# l.net
KiCad netlist of a schematic drawn in EAGLE
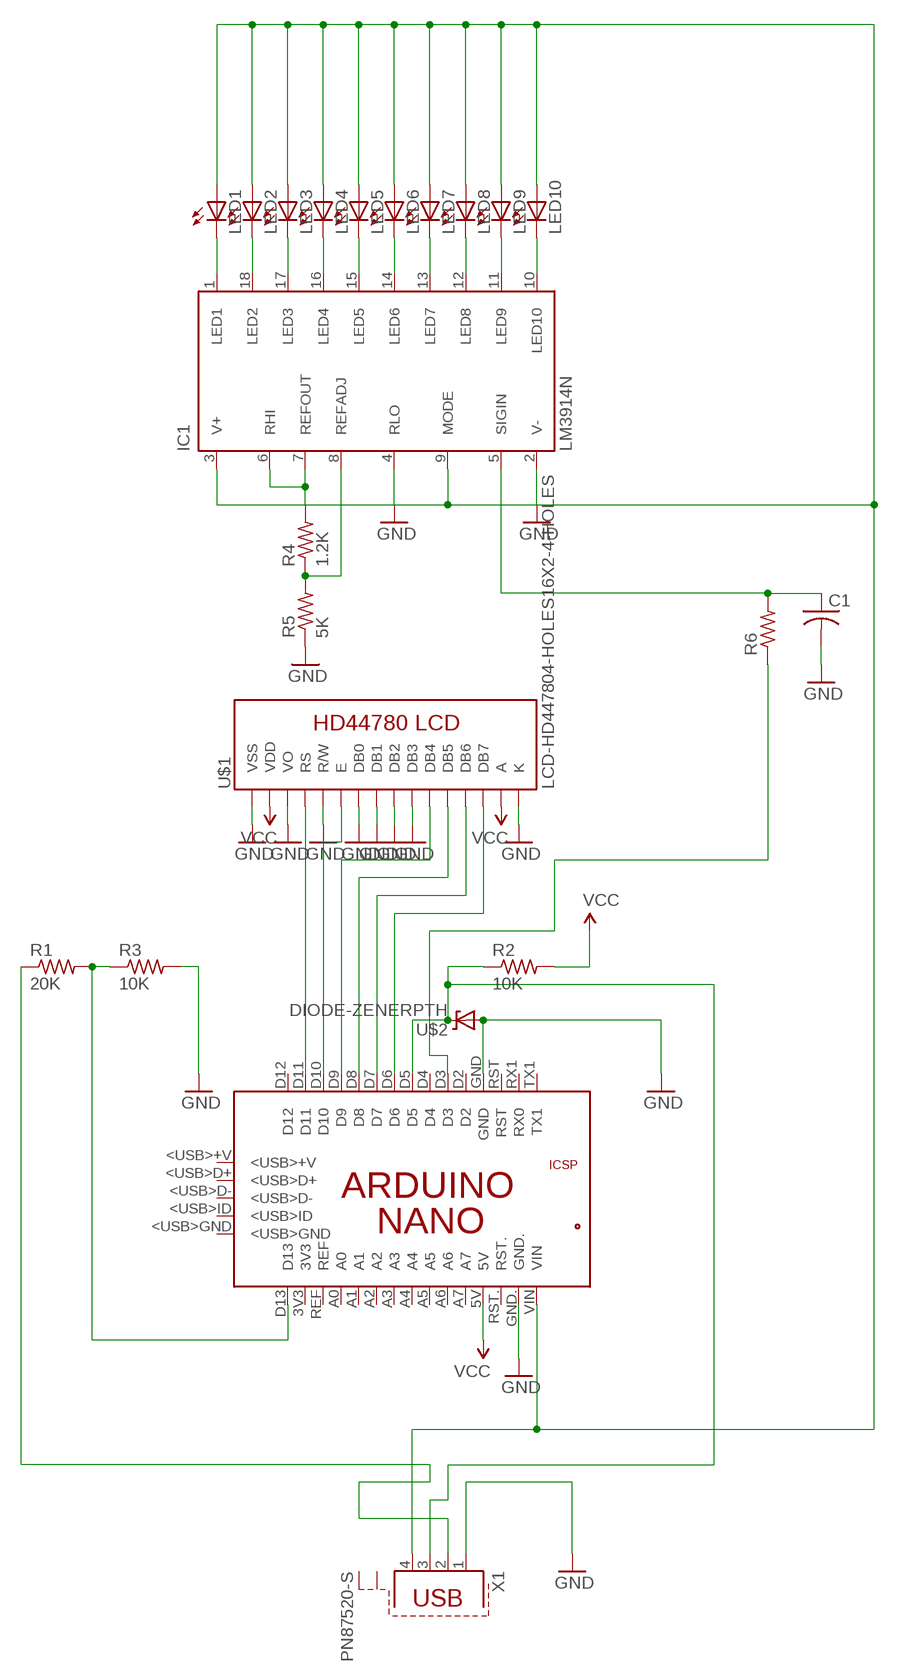
[diagram p0: schematic, sheet 1]

(export (version "E")
  (design (tool "Eeschema 10.0.6"))
  (components
    (comp (ref "C1")
      (value "C-US025-040X050")
      (footprint "eagle-import:C025-040X050")
      (libsource (lib "eagle-import") (part "C-US025-040X050"))
    )
    (comp (ref "IC1")
      (value "LM3914N")
      (footprint "eagle-import:DIL18")
      (libsource (lib "eagle-import") (part "LM391N4"))
    )
    (comp (ref "LED1")
      (value "LED5MM")
      (footprint "eagle-import:LED5MM")
      (libsource (lib "eagle-import") (part "LED5MM"))
    )
    (comp (ref "LED2")
      (value "LED5MM")
      (footprint "eagle-import:LED5MM")
      (libsource (lib "eagle-import") (part "LED5MM"))
    )
    (comp (ref "LED3")
      (value "LED5MM")
      (footprint "eagle-import:LED5MM")
      (libsource (lib "eagle-import") (part "LED5MM"))
    )
    (comp (ref "LED4")
      (value "LED5MM")
      (footprint "eagle-import:LED5MM")
      (libsource (lib "eagle-import") (part "LED5MM"))
    )
    (comp (ref "LED5")
      (value "LED5MM")
      (footprint "eagle-import:LED5MM")
      (libsource (lib "eagle-import") (part "LED5MM"))
    )
    (comp (ref "LED6")
      (value "LED5MM")
      (footprint "eagle-import:LED5MM")
      (libsource (lib "eagle-import") (part "LED5MM"))
    )
    (comp (ref "LED7")
      (value "LED5MM")
      (footprint "eagle-import:LED5MM")
      (libsource (lib "eagle-import") (part "LED5MM"))
    )
    (comp (ref "LED8")
      (value "LED5MM")
      (footprint "eagle-import:LED5MM")
      (libsource (lib "eagle-import") (part "LED5MM"))
    )
    (comp (ref "LED9")
      (value "LED5MM")
      (footprint "eagle-import:LED5MM")
      (libsource (lib "eagle-import") (part "LED5MM"))
    )
    (comp (ref "LED10")
      (value "LED5MM")
      (footprint "eagle-import:LED5MM")
      (libsource (lib "eagle-import") (part "LED5MM"))
    )
    (comp (ref "PCB1")
      (value "ARDUINO_NANO")
      (footprint "eagle-import:ARDUINO_NANO")
      (libsource (lib "eagle-import") (part "ARDUINO_NANO"))
    )
    (comp (ref "R1")
      (value "20K")
      (footprint "eagle-import:0204_7")
      (libsource (lib "eagle-import") (part "R-US_0204/7"))
    )
    (comp (ref "R2")
      (value "10K")
      (footprint "eagle-import:0204_7")
      (libsource (lib "eagle-import") (part "R-US_0204/7"))
    )
    (comp (ref "R3")
      (value "10K")
      (footprint "eagle-import:0204_7")
      (libsource (lib "eagle-import") (part "R-US_0204/7"))
    )
    (comp (ref "R4")
      (value "1.2K")
      (footprint "eagle-import:0204_7")
      (libsource (lib "eagle-import") (part "R-US_0204/7"))
    )
    (comp (ref "R5")
      (value "5K")
      (footprint "eagle-import:0204_7")
      (libsource (lib "eagle-import") (part "R-US_0204/7"))
    )
    (comp (ref "R6")
      (value "R-US_0204/7")
      (footprint "eagle-import:0204_7")
      (libsource (lib "eagle-import") (part "R-US_0204/7"))
    )
    (comp (ref "U$1")
      (value "LCD-HD447804-HOLES16X2-4-HOLES")
      (footprint "eagle-import:LCD-16X2-4HOLES")
      (libsource (lib "eagle-import") (part "LCD-HD4478016X2-4-HOLES4-HOLES"))
    )
    (comp (ref "U$2")
      (value "DIODE-ZENERPTH")
      (footprint "eagle-import:DIODE-ZENER")
      (libsource (lib "eagle-import") (part "DIODE-ZENERPTH"))
    )
    (comp (ref "X1")
      (value "PN87520-S")
      (footprint "eagle-import:PN87520-S")
      (libsource (lib "eagle-import") (part "PN87520-S"))
    )
  )
  (nets
    (net (code "1") (name "GND") (class "Default")
      (node (ref "C1") (pin "2") (pinfunction "2_2") (pintype "passive"))
      (node (ref "IC1") (pin "2") (pinfunction "V-_2") (pintype "power_in"))
      (node (ref "IC1") (pin "4") (pinfunction "RLO_4") (pintype "input"))
      (node (ref "PCB1") (pin "GND") (pinfunction "GND_GND") (pintype "bidirectional"))
      (node (ref "PCB1") (pin "GND.") (pinfunction "GND._GND.") (pintype "bidirectional"))
      (node (ref "R3") (pin "2") (pinfunction "2_2") (pintype "passive"))
      (node (ref "R5") (pin "1") (pinfunction "1_1") (pintype "passive"))
      (node (ref "U$1") (pin "1") (pinfunction "VSS_1") (pintype "power_in"))
      (node (ref "U$1") (pin "10") (pinfunction "DB3_10") (pintype "bidirectional"))
      (node (ref "U$1") (pin "16") (pinfunction "K_16") (pintype "power_in"))
      (node (ref "U$1") (pin "3") (pinfunction "VO_3") (pintype "bidirectional"))
      (node (ref "U$1") (pin "5") (pinfunction "R/W_5") (pintype "input"))
      (node (ref "U$1") (pin "7") (pinfunction "DB0_7") (pintype "bidirectional"))
      (node (ref "U$1") (pin "8") (pinfunction "DB1_8") (pintype "bidirectional"))
      (node (ref "U$1") (pin "9") (pinfunction "DB2_9") (pintype "bidirectional"))
      (node (ref "U$2") (pin "P$2") (pinfunction "A_P$2") (pintype "passive"))
      (node (ref "X1") (pin "1") (pinfunction "1_1") (pintype "passive"))
    )
    (net (code "2") (name "Net-(IC1-LED1)") (class "Default")
      (node (ref "IC1") (pin "1") (pinfunction "LED1_1") (pintype "output"))
      (node (ref "LED1") (pin "K") (pinfunction "C_K") (pintype "passive"))
    )
    (net (code "3") (name "Net-(IC1-LED2)") (class "Default")
      (node (ref "IC1") (pin "18") (pinfunction "LED2_18") (pintype "output"))
      (node (ref "LED2") (pin "K") (pinfunction "C_K") (pintype "passive"))
    )
    (net (code "4") (name "Net-(IC1-LED3)") (class "Default")
      (node (ref "IC1") (pin "17") (pinfunction "LED3_17") (pintype "output"))
      (node (ref "LED3") (pin "K") (pinfunction "C_K") (pintype "passive"))
    )
    (net (code "5") (name "Net-(IC1-LED4)") (class "Default")
      (node (ref "IC1") (pin "16") (pinfunction "LED4_16") (pintype "output"))
      (node (ref "LED4") (pin "K") (pinfunction "C_K") (pintype "passive"))
    )
    (net (code "6") (name "Net-(IC1-LED5)") (class "Default")
      (node (ref "IC1") (pin "15") (pinfunction "LED5_15") (pintype "output"))
      (node (ref "LED5") (pin "K") (pinfunction "C_K") (pintype "passive"))
    )
    (net (code "7") (name "Net-(IC1-LED6)") (class "Default")
      (node (ref "IC1") (pin "14") (pinfunction "LED6_14") (pintype "output"))
      (node (ref "LED6") (pin "K") (pinfunction "C_K") (pintype "passive"))
    )
    (net (code "8") (name "Net-(IC1-LED7)") (class "Default")
      (node (ref "IC1") (pin "13") (pinfunction "LED7_13") (pintype "output"))
      (node (ref "LED7") (pin "K") (pinfunction "C_K") (pintype "passive"))
    )
    (net (code "9") (name "Net-(IC1-LED8)") (class "Default")
      (node (ref "IC1") (pin "12") (pinfunction "LED8_12") (pintype "output"))
      (node (ref "LED8") (pin "K") (pinfunction "C_K") (pintype "passive"))
    )
    (net (code "10") (name "Net-(IC1-LED9)") (class "Default")
      (node (ref "IC1") (pin "11") (pinfunction "LED9_11") (pintype "output"))
      (node (ref "LED9") (pin "K") (pinfunction "C_K") (pintype "passive"))
    )
    (net (code "11") (name "Net-(IC1-LED10)") (class "Default")
      (node (ref "IC1") (pin "10") (pinfunction "LED10_10") (pintype "output"))
      (node (ref "LED10") (pin "K") (pinfunction "C_K") (pintype "passive"))
    )
    (net (code "12") (name "Net-(IC1-MODE)") (class "Default")
      (node (ref "IC1") (pin "3") (pinfunction "V+_3") (pintype "power_in"))
      (node (ref "IC1") (pin "9") (pinfunction "MODE_9") (pintype "input"))
      (node (ref "LED1") (pin "A") (pinfunction "A_A") (pintype "passive"))
      (node (ref "LED10") (pin "A") (pinfunction "A_A") (pintype "passive"))
      (node (ref "LED2") (pin "A") (pinfunction "A_A") (pintype "passive"))
      (node (ref "LED3") (pin "A") (pinfunction "A_A") (pintype "passive"))
      (node (ref "LED4") (pin "A") (pinfunction "A_A") (pintype "passive"))
      (node (ref "LED5") (pin "A") (pinfunction "A_A") (pintype "passive"))
      (node (ref "LED6") (pin "A") (pinfunction "A_A") (pintype "passive"))
      (node (ref "LED7") (pin "A") (pinfunction "A_A") (pintype "passive"))
      (node (ref "LED8") (pin "A") (pinfunction "A_A") (pintype "passive"))
      (node (ref "LED9") (pin "A") (pinfunction "A_A") (pintype "passive"))
      (node (ref "PCB1") (pin "VIN") (pinfunction "VIN_VIN") (pintype "bidirectional"))
      (node (ref "X1") (pin "4") (pinfunction "4_4") (pintype "passive"))
    )
    (net (code "13") (name "Net-(IC1-REFADJ)") (class "Default")
      (node (ref "IC1") (pin "8") (pinfunction "REFADJ_8") (pintype "passive"))
      (node (ref "R4") (pin "1") (pinfunction "1_1") (pintype "passive"))
      (node (ref "R5") (pin "2") (pinfunction "2_2") (pintype "passive"))
    )
    (net (code "14") (name "Net-(IC1-REFOUT)") (class "Default")
      (node (ref "IC1") (pin "6") (pinfunction "RHI_6") (pintype "input"))
      (node (ref "IC1") (pin "7") (pinfunction "REFOUT_7") (pintype "output"))
      (node (ref "R4") (pin "2") (pinfunction "2_2") (pintype "passive"))
    )
    (net (code "15") (name "Net-(IC1-SIGIN)") (class "Default")
      (node (ref "C1") (pin "1") (pinfunction "1_1") (pintype "passive"))
      (node (ref "IC1") (pin "5") (pinfunction "SIGIN_5") (pintype "input"))
      (node (ref "R6") (pin "2") (pinfunction "2_2") (pintype "passive"))
    )
    (net (code "16") (name "Net-(PCB1-PadD3)") (class "Default")
      (node (ref "PCB1") (pin "D3") (pinfunction "D3_D3") (pintype "bidirectional"))
      (node (ref "R6") (pin "1") (pinfunction "1_1") (pintype "passive"))
    )
    (net (code "17") (name "Net-(PCB1-PadD13)") (class "Default")
      (node (ref "PCB1") (pin "D13") (pinfunction "D13_D13") (pintype "bidirectional"))
      (node (ref "R1") (pin "2") (pinfunction "2_2") (pintype "passive"))
      (node (ref "R3") (pin "1") (pinfunction "1_1") (pintype "passive"))
    )
    (net (code "18") (name "Net-(R1-Pad1)") (class "Default")
      (node (ref "R1") (pin "1") (pinfunction "1_1") (pintype "passive"))
      (node (ref "X1") (pin "2") (pinfunction "2_2") (pintype "passive"))
    )
    (net (code "19") (name "Net-(U$1-DB4)") (class "Default")
      (node (ref "PCB1") (pin "D9") (pinfunction "D9_D9") (pintype "bidirectional"))
      (node (ref "U$1") (pin "11") (pinfunction "DB4_11") (pintype "bidirectional"))
    )
    (net (code "20") (name "Net-(U$1-DB5)") (class "Default")
      (node (ref "PCB1") (pin "D8") (pinfunction "D8_D8") (pintype "bidirectional"))
      (node (ref "U$1") (pin "12") (pinfunction "DB5_12") (pintype "bidirectional"))
    )
    (net (code "21") (name "Net-(U$1-DB6)") (class "Default")
      (node (ref "PCB1") (pin "D7") (pinfunction "D7_D7") (pintype "bidirectional"))
      (node (ref "U$1") (pin "13") (pinfunction "DB6_13") (pintype "bidirectional"))
    )
    (net (code "22") (name "Net-(U$1-DB7)") (class "Default")
      (node (ref "PCB1") (pin "D6") (pinfunction "D6_D6") (pintype "bidirectional"))
      (node (ref "U$1") (pin "14") (pinfunction "DB7_14") (pintype "bidirectional"))
    )
    (net (code "23") (name "Net-(U$1-E)") (class "Default")
      (node (ref "PCB1") (pin "D10") (pinfunction "D10_D10") (pintype "bidirectional"))
      (node (ref "U$1") (pin "6") (pinfunction "E_6") (pintype "input"))
    )
    (net (code "24") (name "Net-(U$1-RS)") (class "Default")
      (node (ref "PCB1") (pin "D11") (pinfunction "D11_D11") (pintype "bidirectional"))
      (node (ref "U$1") (pin "4") (pinfunction "RS_4") (pintype "input"))
    )
    (net (code "25") (name "Net-(U$2-C)") (class "Default")
      (node (ref "PCB1") (pin "D5") (pinfunction "D5_D5") (pintype "bidirectional"))
      (node (ref "R2") (pin "1") (pinfunction "1_1") (pintype "passive"))
      (node (ref "U$2") (pin "P$1") (pinfunction "C_P$1") (pintype "passive"))
      (node (ref "X1") (pin "3") (pinfunction "3_3") (pintype "passive"))
    )
    (net (code "26") (name "VCC") (class "Default")
      (node (ref "PCB1") (pin "5V") (pinfunction "5V_5V") (pintype "bidirectional"))
      (node (ref "R2") (pin "2") (pinfunction "2_2") (pintype "passive"))
      (node (ref "U$1") (pin "15") (pinfunction "A_15") (pintype "power_in"))
      (node (ref "U$1") (pin "2") (pinfunction "VDD_2") (pintype "power_in"))
    )
    (net (code "27") (name "unconnected-(PCB1-Pad3V3)") (class "Default")
      (node (ref "PCB1") (pin "3V3") (pinfunction "3V3_3V3") (pintype "bidirectional"))
    )
    (net (code "28") (name "unconnected-(PCB1-Pad5V.)") (class "Default")
      (node (ref "PCB1") (pin "5V.") (pinfunction "5V._5V.") (pintype "bidirectional"))
    )
    (net (code "29") (name "unconnected-(PCB1-Pad<USB>+V)") (class "Default")
      (node (ref "PCB1") (pin "<USB>+V") (pinfunction "<USB>+V_<USB>+V") (pintype "bidirectional"))
    )
    (net (code "30") (name "unconnected-(PCB1-Pad<USB>D+)") (class "Default")
      (node (ref "PCB1") (pin "<USB>D+") (pinfunction "<USB>D+_<USB>D+") (pintype "bidirectional"))
    )
    (net (code "31") (name "unconnected-(PCB1-Pad<USB>D-)") (class "Default")
      (node (ref "PCB1") (pin "<USB>D-") (pinfunction "<USB>D-_<USB>D-") (pintype "bidirectional"))
    )
    (net (code "32") (name "unconnected-(PCB1-Pad<USB>GND)") (class "Default")
      (node (ref "PCB1") (pin "<USB>GND") (pinfunction "<USB>GND_<USB>GND") (pintype "bidirectional"))
    )
    (net (code "33") (name "unconnected-(PCB1-Pad<USB>ID)") (class "Default")
      (node (ref "PCB1") (pin "<USB>ID") (pinfunction "<USB>ID_<USB>ID") (pintype "bidirectional"))
    )
    (net (code "34") (name "unconnected-(PCB1-PadA0)") (class "Default")
      (node (ref "PCB1") (pin "A0") (pinfunction "A0_A0") (pintype "bidirectional"))
    )
    (net (code "35") (name "unconnected-(PCB1-PadA1)") (class "Default")
      (node (ref "PCB1") (pin "A1") (pinfunction "A1_A1") (pintype "bidirectional"))
    )
    (net (code "36") (name "unconnected-(PCB1-PadA2)") (class "Default")
      (node (ref "PCB1") (pin "A2") (pinfunction "A2_A2") (pintype "bidirectional"))
    )
    (net (code "37") (name "unconnected-(PCB1-PadA3)") (class "Default")
      (node (ref "PCB1") (pin "A3") (pinfunction "A3_A3") (pintype "bidirectional"))
    )
    (net (code "38") (name "unconnected-(PCB1-PadA4)") (class "Default")
      (node (ref "PCB1") (pin "A4") (pinfunction "A4_A4") (pintype "bidirectional"))
    )
    (net (code "39") (name "unconnected-(PCB1-PadA5)") (class "Default")
      (node (ref "PCB1") (pin "A5") (pinfunction "A5_A5") (pintype "bidirectional"))
    )
    (net (code "40") (name "unconnected-(PCB1-PadA6)") (class "Default")
      (node (ref "PCB1") (pin "A6") (pinfunction "A6_A6") (pintype "bidirectional"))
    )
    (net (code "41") (name "unconnected-(PCB1-PadA7)") (class "Default")
      (node (ref "PCB1") (pin "A7") (pinfunction "A7_A7") (pintype "bidirectional"))
    )
    (net (code "42") (name "unconnected-(PCB1-PadD2)") (class "Default")
      (node (ref "PCB1") (pin "D2") (pinfunction "D2_D2") (pintype "bidirectional"))
    )
    (net (code "43") (name "unconnected-(PCB1-PadD4)") (class "Default")
      (node (ref "PCB1") (pin "D4") (pinfunction "D4_D4") (pintype "bidirectional"))
    )
    (net (code "44") (name "unconnected-(PCB1-PadD12)") (class "Default")
      (node (ref "PCB1") (pin "D12") (pinfunction "D12_D12") (pintype "bidirectional"))
    )
    (net (code "45") (name "unconnected-(PCB1-PadGND_)") (class "Default")
      (node (ref "PCB1") (pin "GND_") (pinfunction "GND__GND_") (pintype "bidirectional"))
    )
    (net (code "46") (name "unconnected-(PCB1-PadMISO)") (class "Default")
      (node (ref "PCB1") (pin "MISO") (pinfunction "MISO_MISO") (pintype "bidirectional"))
    )
    (net (code "47") (name "unconnected-(PCB1-PadMOSI)") (class "Default")
      (node (ref "PCB1") (pin "MOSI") (pinfunction "MOSI_MOSI") (pintype "bidirectional"))
    )
    (net (code "48") (name "unconnected-(PCB1-PadREF)") (class "Default")
      (node (ref "PCB1") (pin "REF") (pinfunction "REF_REF") (pintype "bidirectional"))
    )
    (net (code "49") (name "unconnected-(PCB1-PadRESET..)") (class "Default")
      (node (ref "PCB1") (pin "RESET..") (pinfunction "RESET.._RESET..") (pintype "bidirectional"))
    )
    (net (code "50") (name "unconnected-(PCB1-PadRST)") (class "Default")
      (node (ref "PCB1") (pin "RST") (pinfunction "RST_RST") (pintype "bidirectional"))
    )
    (net (code "51") (name "unconnected-(PCB1-PadRST.)") (class "Default")
      (node (ref "PCB1") (pin "RST.") (pinfunction "RST._RST.") (pintype "bidirectional"))
    )
    (net (code "52") (name "unconnected-(PCB1-PadSCK)") (class "Default")
      (node (ref "PCB1") (pin "SCK") (pinfunction "SCK_SCK") (pintype "bidirectional"))
    )
    (net (code "53") (name "unconnected-(PCB1-PadTX1)") (class "Default")
      (node (ref "PCB1") (pin "TX1") (pinfunction "TX1_TX1") (pintype "bidirectional"))
    )
    (net (code "54") (name "unconnected-(PCB1-RX0-PadRX1)") (class "Default")
      (node (ref "PCB1") (pin "RX1") (pinfunction "RX0_RX1") (pintype "bidirectional"))
    )
    (net (code "55") (name "unconnected-(X1-PadS1)") (class "Default")
      (node (ref "X1") (pin "S1") (pinfunction "S1_S1") (pintype "passive"))
    )
    (net (code "56") (name "unconnected-(X1-PadS2)") (class "Default")
      (node (ref "X1") (pin "S2") (pinfunction "S2_S2") (pintype "passive"))
    )
  )
)
